# LED_WITH_8051.net
KiCad netlist of a schematic drawn in EAGLE
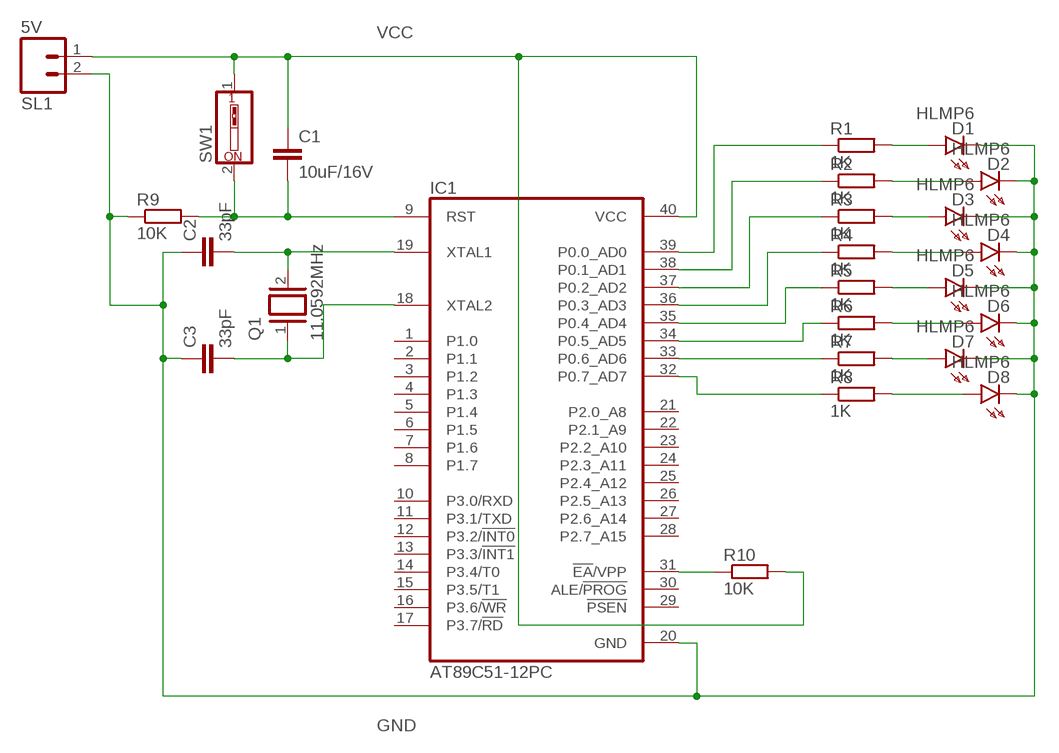
[diagram p0: schematic, sheet 1]

(export (version "E")
  (design (tool "Eeschema 10.0.6"))
  (components
    (comp (ref "C1")
      (value "10uF/16V")
      (footprint "eagle-import:C025-025X050")
      (libsource (lib "eagle-import") (part "C-EU025-025X050"))
    )
    (comp (ref "C2")
      (value "33pF")
      (footprint "eagle-import:C025-025X050")
      (libsource (lib "eagle-import") (part "C-EU025-025X050"))
    )
    (comp (ref "C3")
      (value "33pF")
      (footprint "eagle-import:C025-025X050")
      (libsource (lib "eagle-import") (part "C-EU025-025X050"))
    )
    (comp (ref "D1")
      (value "HLMP6")
      (footprint "eagle-import:HLMP6")
      (fields (field (name "MF") "AGILENT TECHNOLOGIES") (field (name "MPN") "HLMP-6500"))
      (libsource (lib "eagle-import") (part "HLMP6"))
    )
    (comp (ref "D2")
      (value "HLMP6")
      (footprint "eagle-import:HLMP6")
      (fields (field (name "MF") "AGILENT TECHNOLOGIES") (field (name "MPN") "HLMP-6500"))
      (libsource (lib "eagle-import") (part "HLMP6"))
    )
    (comp (ref "D3")
      (value "HLMP6")
      (footprint "eagle-import:HLMP6")
      (fields (field (name "MF") "AGILENT TECHNOLOGIES") (field (name "MPN") "HLMP-6500"))
      (libsource (lib "eagle-import") (part "HLMP6"))
    )
    (comp (ref "D4")
      (value "HLMP6")
      (footprint "eagle-import:HLMP6")
      (fields (field (name "MF") "AGILENT TECHNOLOGIES") (field (name "MPN") "HLMP-6500"))
      (libsource (lib "eagle-import") (part "HLMP6"))
    )
    (comp (ref "D5")
      (value "HLMP6")
      (footprint "eagle-import:HLMP6")
      (fields (field (name "MF") "AGILENT TECHNOLOGIES") (field (name "MPN") "HLMP-6500"))
      (libsource (lib "eagle-import") (part "HLMP6"))
    )
    (comp (ref "D6")
      (value "HLMP6")
      (footprint "eagle-import:HLMP6")
      (fields (field (name "MF") "AGILENT TECHNOLOGIES") (field (name "MPN") "HLMP-6500"))
      (libsource (lib "eagle-import") (part "HLMP6"))
    )
    (comp (ref "D7")
      (value "HLMP6")
      (footprint "eagle-import:HLMP6")
      (fields (field (name "MF") "AGILENT TECHNOLOGIES") (field (name "MPN") "HLMP-6500"))
      (libsource (lib "eagle-import") (part "HLMP6"))
    )
    (comp (ref "D8")
      (value "HLMP6")
      (footprint "eagle-import:HLMP6")
      (fields (field (name "MF") "AGILENT TECHNOLOGIES") (field (name "MPN") "HLMP-6500"))
      (libsource (lib "eagle-import") (part "HLMP6"))
    )
    (comp (ref "IC1")
      (value "AT89C51-12PC")
      (footprint "eagle-import:DIL40")
      (libsource (lib "eagle-import") (part "AT89C51-PC12"))
    )
    (comp (ref "Q1")
      (value "11.0592MHz")
      (footprint "eagle-import:Q")
      (libsource (lib "eagle-import") (part "XTAL"))
    )
    (comp (ref "R1")
      (value "1K")
      (footprint "eagle-import:0204_7")
      (libsource (lib "eagle-import") (part "R-EU_0204/7"))
    )
    (comp (ref "R2")
      (value "1K")
      (footprint "eagle-import:0204_7")
      (libsource (lib "eagle-import") (part "R-EU_0204/7"))
    )
    (comp (ref "R3")
      (value "1K")
      (footprint "eagle-import:0204_7")
      (libsource (lib "eagle-import") (part "R-EU_0204/7"))
    )
    (comp (ref "R4")
      (value "1K")
      (footprint "eagle-import:0204_7")
      (libsource (lib "eagle-import") (part "R-EU_0204/7"))
    )
    (comp (ref "R5")
      (value "1K")
      (footprint "eagle-import:0204_7")
      (libsource (lib "eagle-import") (part "R-EU_0204/7"))
    )
    (comp (ref "R6")
      (value "1K")
      (footprint "eagle-import:0204_7")
      (libsource (lib "eagle-import") (part "R-EU_0204/7"))
    )
    (comp (ref "R7")
      (value "1K")
      (footprint "eagle-import:0204_7")
      (libsource (lib "eagle-import") (part "R-EU_0204/7"))
    )
    (comp (ref "R8")
      (value "1K")
      (footprint "eagle-import:0204_7")
      (libsource (lib "eagle-import") (part "R-EU_0204/7"))
    )
    (comp (ref "R9")
      (value "10K")
      (footprint "eagle-import:0204_7")
      (libsource (lib "eagle-import") (part "R-EU_0204/7"))
    )
    (comp (ref "R10")
      (value "10K")
      (footprint "eagle-import:0204_7")
      (libsource (lib "eagle-import") (part "R-EU_0204/7"))
    )
    (comp (ref "SL1")
      (value "5V")
      (footprint "eagle-import:02P")
      (libsource (lib "eagle-import") (part "M02"))
    )
    (comp (ref "SW1")
      (value "SW_DIP-1")
      (footprint "eagle-import:EDG-01")
      (libsource (lib "eagle-import") (part "SW_DIP-1"))
    )
  )
  (nets
    (net (code "1") (name "/GND") (class "Default")
      (node (ref "C2") (pin "1") (pinfunction "1_1") (pintype "passive"))
      (node (ref "C3") (pin "1") (pinfunction "1_1") (pintype "passive"))
      (node (ref "D1") (pin "K") (pinfunction "K_K") (pintype "passive"))
      (node (ref "D2") (pin "K") (pinfunction "K_K") (pintype "passive"))
      (node (ref "D3") (pin "K") (pinfunction "K_K") (pintype "passive"))
      (node (ref "D4") (pin "K") (pinfunction "K_K") (pintype "passive"))
      (node (ref "D5") (pin "K") (pinfunction "K_K") (pintype "passive"))
      (node (ref "D6") (pin "K") (pinfunction "K_K") (pintype "passive"))
      (node (ref "D7") (pin "K") (pinfunction "K_K") (pintype "passive"))
      (node (ref "D8") (pin "K") (pinfunction "K_K") (pintype "passive"))
      (node (ref "IC1") (pin "20") (pinfunction "GND_20") (pintype "power_in"))
      (node (ref "R9") (pin "1") (pinfunction "1_1") (pintype "passive"))
      (node (ref "SL1") (pin "2") (pinfunction "2_2") (pintype "passive"))
    )
    (net (code "2") (name "/VCC") (class "Default")
      (node (ref "C1") (pin "1") (pinfunction "1_1") (pintype "passive"))
      (node (ref "IC1") (pin "40") (pinfunction "VCC_40") (pintype "power_in"))
      (node (ref "R10") (pin "2") (pinfunction "2_2") (pintype "passive"))
      (node (ref "SL1") (pin "1") (pinfunction "1_1") (pintype "passive"))
      (node (ref "SW1") (pin "1") (pinfunction "1_1") (pintype "passive"))
    )
    (net (code "3") (name "Net-(D1-PadA)") (class "Default")
      (node (ref "D1") (pin "A") (pinfunction "A_A") (pintype "passive"))
      (node (ref "R1") (pin "2") (pinfunction "2_2") (pintype "passive"))
    )
    (net (code "4") (name "Net-(D2-PadA)") (class "Default")
      (node (ref "D2") (pin "A") (pinfunction "A_A") (pintype "passive"))
      (node (ref "R2") (pin "2") (pinfunction "2_2") (pintype "passive"))
    )
    (net (code "5") (name "Net-(D3-PadA)") (class "Default")
      (node (ref "D3") (pin "A") (pinfunction "A_A") (pintype "passive"))
      (node (ref "R3") (pin "2") (pinfunction "2_2") (pintype "passive"))
    )
    (net (code "6") (name "Net-(D4-PadA)") (class "Default")
      (node (ref "D4") (pin "A") (pinfunction "A_A") (pintype "passive"))
      (node (ref "R4") (pin "2") (pinfunction "2_2") (pintype "passive"))
    )
    (net (code "7") (name "Net-(D5-PadA)") (class "Default")
      (node (ref "D5") (pin "A") (pinfunction "A_A") (pintype "passive"))
      (node (ref "R5") (pin "2") (pinfunction "2_2") (pintype "passive"))
    )
    (net (code "8") (name "Net-(D6-PadA)") (class "Default")
      (node (ref "D6") (pin "A") (pinfunction "A_A") (pintype "passive"))
      (node (ref "R6") (pin "2") (pinfunction "2_2") (pintype "passive"))
    )
    (net (code "9") (name "Net-(D7-PadA)") (class "Default")
      (node (ref "D7") (pin "A") (pinfunction "A_A") (pintype "passive"))
      (node (ref "R7") (pin "2") (pinfunction "2_2") (pintype "passive"))
    )
    (net (code "10") (name "Net-(D8-PadA)") (class "Default")
      (node (ref "D8") (pin "A") (pinfunction "A_A") (pintype "passive"))
      (node (ref "R8") (pin "2") (pinfunction "2_2") (pintype "passive"))
    )
    (net (code "11") (name "Net-(IC1-P0.0_AD0)") (class "Default")
      (node (ref "IC1") (pin "39") (pinfunction "P0.0_AD0_39") (pintype "bidirectional"))
      (node (ref "R1") (pin "1") (pinfunction "1_1") (pintype "passive"))
    )
    (net (code "12") (name "Net-(IC1-P0.1_AD1)") (class "Default")
      (node (ref "IC1") (pin "38") (pinfunction "P0.1_AD1_38") (pintype "bidirectional"))
      (node (ref "R2") (pin "1") (pinfunction "1_1") (pintype "passive"))
    )
    (net (code "13") (name "Net-(IC1-P0.2_AD2)") (class "Default")
      (node (ref "IC1") (pin "37") (pinfunction "P0.2_AD2_37") (pintype "bidirectional"))
      (node (ref "R3") (pin "1") (pinfunction "1_1") (pintype "passive"))
    )
    (net (code "14") (name "Net-(IC1-P0.3_AD3)") (class "Default")
      (node (ref "IC1") (pin "36") (pinfunction "P0.3_AD3_36") (pintype "bidirectional"))
      (node (ref "R4") (pin "1") (pinfunction "1_1") (pintype "passive"))
    )
    (net (code "15") (name "Net-(IC1-P0.4_AD4)") (class "Default")
      (node (ref "IC1") (pin "35") (pinfunction "P0.4_AD4_35") (pintype "bidirectional"))
      (node (ref "R5") (pin "1") (pinfunction "1_1") (pintype "passive"))
    )
    (net (code "16") (name "Net-(IC1-P0.5_AD5)") (class "Default")
      (node (ref "IC1") (pin "34") (pinfunction "P0.5_AD5_34") (pintype "bidirectional"))
      (node (ref "R6") (pin "1") (pinfunction "1_1") (pintype "passive"))
    )
    (net (code "17") (name "Net-(IC1-P0.6_AD6)") (class "Default")
      (node (ref "IC1") (pin "33") (pinfunction "P0.6_AD6_33") (pintype "bidirectional"))
      (node (ref "R7") (pin "1") (pinfunction "1_1") (pintype "passive"))
    )
    (net (code "18") (name "Net-(IC1-P0.7_AD7)") (class "Default")
      (node (ref "IC1") (pin "32") (pinfunction "P0.7_AD7_32") (pintype "bidirectional"))
      (node (ref "R8") (pin "1") (pinfunction "1_1") (pintype "passive"))
    )
    (net (code "19") (name "Net-(IC1-RST)") (class "Default")
      (node (ref "C1") (pin "2") (pinfunction "2_2") (pintype "passive"))
      (node (ref "IC1") (pin "9") (pinfunction "RST_9") (pintype "input"))
      (node (ref "R9") (pin "2") (pinfunction "2_2") (pintype "passive"))
      (node (ref "SW1") (pin "2") (pinfunction "2_2") (pintype "passive"))
    )
    (net (code "20") (name "Net-(IC1-XTAL1)") (class "Default")
      (node (ref "C2") (pin "2") (pinfunction "2_2") (pintype "passive"))
      (node (ref "IC1") (pin "19") (pinfunction "XTAL1_19") (pintype "input"))
      (node (ref "Q1") (pin "2") (pinfunction "2_2") (pintype "passive"))
    )
    (net (code "21") (name "Net-(IC1-XTAL2)") (class "Default")
      (node (ref "C3") (pin "2") (pinfunction "2_2") (pintype "passive"))
      (node (ref "IC1") (pin "18") (pinfunction "XTAL2_18") (pintype "input"))
      (node (ref "Q1") (pin "1") (pinfunction "1_1") (pintype "passive"))
    )
    (net (code "22") (name "Net-(IC1-~{EA}{slash}VPP)") (class "Default")
      (node (ref "IC1") (pin "31") (pinfunction "~{EA}/VPP_31") (pintype "input"))
      (node (ref "R10") (pin "1") (pinfunction "1_1") (pintype "passive"))
    )
    (net (code "23") (name "unconnected-(IC1-ALE{slash}~{PROG}-Pad30)") (class "Default")
      (node (ref "IC1") (pin "30") (pinfunction "ALE/~{PROG}_30") (pintype "output"))
    )
    (net (code "24") (name "unconnected-(IC1-P1.0-Pad1)") (class "Default")
      (node (ref "IC1") (pin "1") (pinfunction "P1.0_1") (pintype "bidirectional"))
    )
    (net (code "25") (name "unconnected-(IC1-P1.1-Pad2)") (class "Default")
      (node (ref "IC1") (pin "2") (pinfunction "P1.1_2") (pintype "bidirectional"))
    )
    (net (code "26") (name "unconnected-(IC1-P1.2-Pad3)") (class "Default")
      (node (ref "IC1") (pin "3") (pinfunction "P1.2_3") (pintype "bidirectional"))
    )
    (net (code "27") (name "unconnected-(IC1-P1.3-Pad4)") (class "Default")
      (node (ref "IC1") (pin "4") (pinfunction "P1.3_4") (pintype "bidirectional"))
    )
    (net (code "28") (name "unconnected-(IC1-P1.4-Pad5)") (class "Default")
      (node (ref "IC1") (pin "5") (pinfunction "P1.4_5") (pintype "bidirectional"))
    )
    (net (code "29") (name "unconnected-(IC1-P1.5-Pad6)") (class "Default")
      (node (ref "IC1") (pin "6") (pinfunction "P1.5_6") (pintype "bidirectional"))
    )
    (net (code "30") (name "unconnected-(IC1-P1.6-Pad7)") (class "Default")
      (node (ref "IC1") (pin "7") (pinfunction "P1.6_7") (pintype "bidirectional"))
    )
    (net (code "31") (name "unconnected-(IC1-P1.7-Pad8)") (class "Default")
      (node (ref "IC1") (pin "8") (pinfunction "P1.7_8") (pintype "bidirectional"))
    )
    (net (code "32") (name "unconnected-(IC1-P2.0_A8-Pad21)") (class "Default")
      (node (ref "IC1") (pin "21") (pinfunction "P2.0_A8_21") (pintype "bidirectional"))
    )
    (net (code "33") (name "unconnected-(IC1-P2.1_A9-Pad22)") (class "Default")
      (node (ref "IC1") (pin "22") (pinfunction "P2.1_A9_22") (pintype "bidirectional"))
    )
    (net (code "34") (name "unconnected-(IC1-P2.2_A10-Pad23)") (class "Default")
      (node (ref "IC1") (pin "23") (pinfunction "P2.2_A10_23") (pintype "bidirectional"))
    )
    (net (code "35") (name "unconnected-(IC1-P2.3_A11-Pad24)") (class "Default")
      (node (ref "IC1") (pin "24") (pinfunction "P2.3_A11_24") (pintype "bidirectional"))
    )
    (net (code "36") (name "unconnected-(IC1-P2.4_A12-Pad25)") (class "Default")
      (node (ref "IC1") (pin "25") (pinfunction "P2.4_A12_25") (pintype "bidirectional"))
    )
    (net (code "37") (name "unconnected-(IC1-P2.5_A13-Pad26)") (class "Default")
      (node (ref "IC1") (pin "26") (pinfunction "P2.5_A13_26") (pintype "bidirectional"))
    )
    (net (code "38") (name "unconnected-(IC1-P2.6_A14-Pad27)") (class "Default")
      (node (ref "IC1") (pin "27") (pinfunction "P2.6_A14_27") (pintype "bidirectional"))
    )
    (net (code "39") (name "unconnected-(IC1-P2.7_A15-Pad28)") (class "Default")
      (node (ref "IC1") (pin "28") (pinfunction "P2.7_A15_28") (pintype "bidirectional"))
    )
    (net (code "40") (name "unconnected-(IC1-P3.0{slash}RXD-Pad10)") (class "Default")
      (node (ref "IC1") (pin "10") (pinfunction "P3.0/RXD_10") (pintype "bidirectional"))
    )
    (net (code "41") (name "unconnected-(IC1-P3.1{slash}TXD-Pad11)") (class "Default")
      (node (ref "IC1") (pin "11") (pinfunction "P3.1/TXD_11") (pintype "bidirectional"))
    )
    (net (code "42") (name "unconnected-(IC1-P3.2{slash}~{INT0}-Pad12)") (class "Default")
      (node (ref "IC1") (pin "12") (pinfunction "P3.2/~{INT0}_12") (pintype "bidirectional"))
    )
    (net (code "43") (name "unconnected-(IC1-P3.3{slash}~{INT1}-Pad13)") (class "Default")
      (node (ref "IC1") (pin "13") (pinfunction "P3.3/~{INT1}_13") (pintype "bidirectional"))
    )
    (net (code "44") (name "unconnected-(IC1-P3.4{slash}T0-Pad14)") (class "Default")
      (node (ref "IC1") (pin "14") (pinfunction "P3.4/T0_14") (pintype "bidirectional"))
    )
    (net (code "45") (name "unconnected-(IC1-P3.5{slash}T1-Pad15)") (class "Default")
      (node (ref "IC1") (pin "15") (pinfunction "P3.5/T1_15") (pintype "bidirectional"))
    )
    (net (code "46") (name "unconnected-(IC1-P3.6{slash}~{WR}-Pad16)") (class "Default")
      (node (ref "IC1") (pin "16") (pinfunction "P3.6/~{WR}_16") (pintype "bidirectional"))
    )
    (net (code "47") (name "unconnected-(IC1-P3.7{slash}~{RD}-Pad17)") (class "Default")
      (node (ref "IC1") (pin "17") (pinfunction "P3.7/~{RD}_17") (pintype "bidirectional"))
    )
    (net (code "48") (name "unconnected-(IC1-~{PSEN}-Pad29)") (class "Default")
      (node (ref "IC1") (pin "29") (pinfunction "~{PSEN}_29") (pintype "output"))
    )
  )
)
